# Memory.net
KiCad netlist of a schematic drawn in Altium Designer
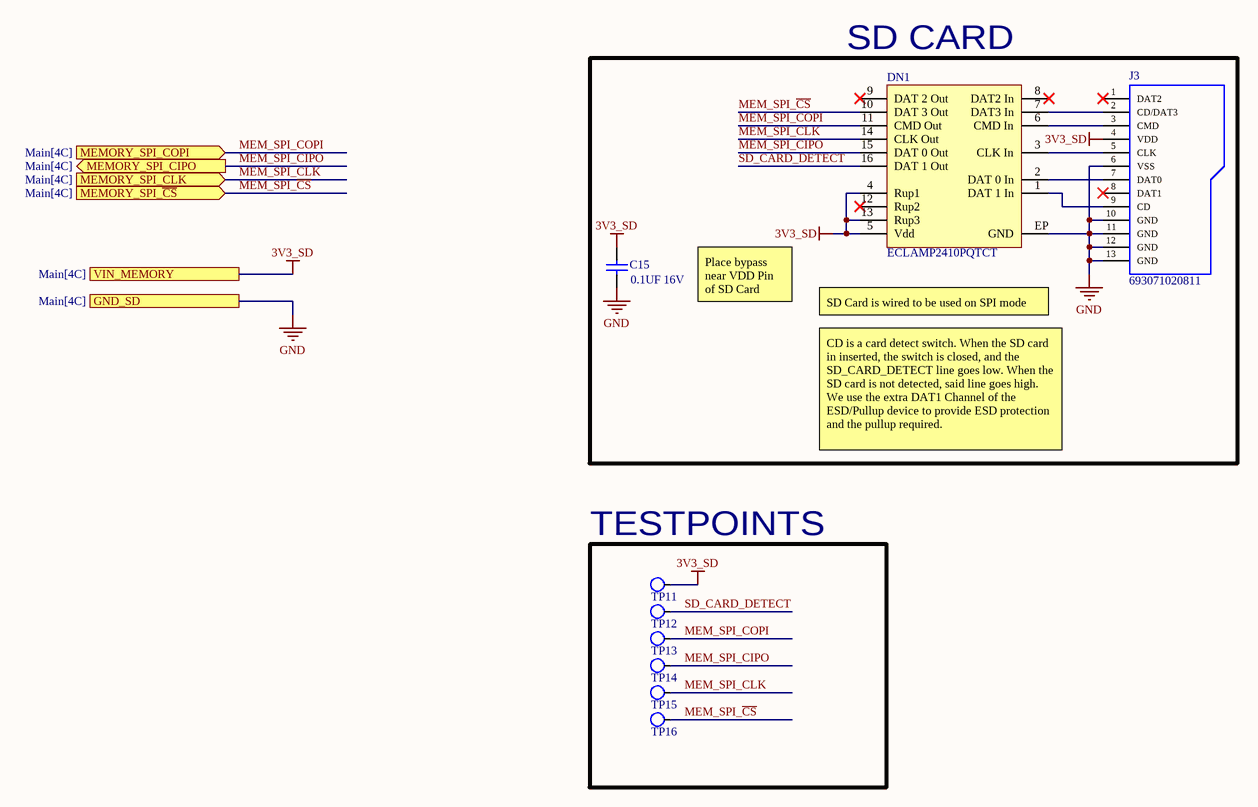
[diagram p0: Memory.SchDoc]

(export (version "E")
  (design (tool "Eeschema 10.0.6"))
  (components
    (comp (ref "C15")
      (value "0.1UF 16V")
      (footprint "0603_CAP")
      (description "Capacitor Surface Mount 0603 Footprint 0.1UF 16V 10% Tolerance Ceramic X7R")
      (fields (field (name "VOLTAGE") "16V") (field (name "MANUFACTURER") "Various"))
      (libsource (lib "University of Pennsylvania (ESE Labs)") (part "cap"))
    )
    (comp (ref "DN1")
      (value "ECLAMP2410PQTCT")
      (footprint "ECLAMP2410PQTCT-Footprint-1")
      (description "Trans Voltage Suppressor Diode, 5V V(RWM), Bidirectional, 7 Element, Silicon with EMI Filter")
      (libsource (lib "University of Pennsylvania (ESE)") (part "ECLAMP2410PQTCT-Symbol-1"))
    )
    (comp (ref "J3")
      (value "693071020811")
      (footprint "693071020811")
      (description "WR-CRD Micro SD Card Connector Push & Push")
      (fields (field (name "PUBLISHER") "Wurth Elektronik"))
      (libsource (lib "University of Pennsylvania (ESE)") (part "CMP-CON-00115-2"))
    )
    (comp (ref "TP11")
      (value "Testpad")
      (footprint "SMT Testpoint, 50mil")
      (description "Test Pad/Point (Testpoint, Testpad), for probing")
      (libsource (lib "University of Pennsylvania (ESE)") (part "30mm Test Pad"))
    )
    (comp (ref "TP12")
      (value "Testpad")
      (footprint "SMT Testpoint, 50mil")
      (description "Test Pad/Point (Testpoint, Testpad), for probing")
      (libsource (lib "University of Pennsylvania (ESE)") (part "30mm Test Pad"))
    )
    (comp (ref "TP13")
      (value "Testpad")
      (footprint "SMT Testpoint, 50mil")
      (description "Test Pad/Point (Testpoint, Testpad), for probing")
      (libsource (lib "University of Pennsylvania (ESE)") (part "30mm Test Pad"))
    )
    (comp (ref "TP14")
      (value "Testpad")
      (footprint "SMT Testpoint, 50mil")
      (description "Test Pad/Point (Testpoint, Testpad), for probing")
      (libsource (lib "University of Pennsylvania (ESE)") (part "30mm Test Pad"))
    )
    (comp (ref "TP15")
      (value "Testpad")
      (footprint "SMT Testpoint, 50mil")
      (description "Test Pad/Point (Testpoint, Testpad), for probing")
      (libsource (lib "University of Pennsylvania (ESE)") (part "30mm Test Pad"))
    )
    (comp (ref "TP16")
      (value "Testpad")
      (footprint "SMT Testpoint, 50mil")
      (description "Test Pad/Point (Testpoint, Testpad), for probing")
      (libsource (lib "University of Pennsylvania (ESE)") (part "30mm Test Pad"))
    )
  )
  (nets
    (net (code "1") (name "/MEM_SPI_CIPO") (class "Default")
      (node (ref "DN1") (pin "15") (pinfunction "DAT_0_Out_15") (pintype "passive"))
      (node (ref "TP14") (pin "1") (pinfunction "1_1") (pintype "passive"))
    )
    (net (code "2") (name "/MEM_SPI_CLK") (class "Default")
      (node (ref "DN1") (pin "14") (pinfunction "CLK_Out_14") (pintype "passive"))
      (node (ref "TP15") (pin "1") (pinfunction "1_1") (pintype "passive"))
    )
    (net (code "3") (name "/MEM_SPI_COPI") (class "Default")
      (node (ref "DN1") (pin "11") (pinfunction "CMD_Out_11") (pintype "passive"))
      (node (ref "TP13") (pin "1") (pinfunction "1_1") (pintype "passive"))
    )
    (net (code "4") (name "/MEM_SPI_~{CS}") (class "Default")
      (node (ref "DN1") (pin "10") (pinfunction "DAT_3_Out_10") (pintype "passive"))
      (node (ref "TP16") (pin "1") (pinfunction "1_1") (pintype "passive"))
    )
    (net (code "5") (name "/SD_CARD_DETECT") (class "Default")
      (node (ref "DN1") (pin "16") (pinfunction "DAT_1_Out_16") (pintype "passive"))
      (node (ref "TP12") (pin "1") (pinfunction "1_1") (pintype "passive"))
    )
    (net (code "6") (name "3V3_SD") (class "Default")
      (node (ref "C15") (pin "2") (pinfunction "2_2") (pintype "passive"))
      (node (ref "DN1") (pin "13") (pinfunction "Rup3_13") (pintype "power_in"))
      (node (ref "DN1") (pin "4") (pinfunction "Rup1_4") (pintype "power_in"))
      (node (ref "DN1") (pin "5") (pinfunction "Vdd_5") (pintype "power_in"))
      (node (ref "J3") (pin "4") (pinfunction "VDD_4") (pintype "passive"))
      (node (ref "TP11") (pin "1") (pinfunction "1_1") (pintype "passive"))
    )
    (net (code "7") (name "GND") (class "Default")
      (node (ref "C15") (pin "1") (pinfunction "1_1") (pintype "passive"))
      (node (ref "DN1") (pin "EP") (pinfunction "GND_EP") (pintype "power_in"))
      (node (ref "J3") (pin "10") (pinfunction "GND_10") (pintype "passive"))
      (node (ref "J3") (pin "11") (pinfunction "GND_11") (pintype "passive"))
      (node (ref "J3") (pin "12") (pinfunction "GND_12") (pintype "passive"))
      (node (ref "J3") (pin "13") (pinfunction "GND_13") (pintype "passive"))
      (node (ref "J3") (pin "6") (pinfunction "VSS_6") (pintype "passive"))
    )
    (net (code "8") (name "Net-(DN1-CLK_In)") (class "Default")
      (node (ref "DN1") (pin "3") (pinfunction "CLK_In_3") (pintype "passive"))
      (node (ref "J3") (pin "5") (pinfunction "CLK_5") (pintype "passive"))
    )
    (net (code "9") (name "Net-(DN1-CMD_In)") (class "Default")
      (node (ref "DN1") (pin "6") (pinfunction "CMD_In_6") (pintype "passive"))
      (node (ref "J3") (pin "3") (pinfunction "CMD_3") (pintype "passive"))
    )
    (net (code "10") (name "Net-(DN1-DAT3_In)") (class "Default")
      (node (ref "DN1") (pin "7") (pinfunction "DAT3_In_7") (pintype "passive"))
      (node (ref "J3") (pin "2") (pinfunction "CD/DAT3_2") (pintype "passive"))
    )
    (net (code "11") (name "Net-(DN1-DAT_0_In)") (class "Default")
      (node (ref "DN1") (pin "2") (pinfunction "DAT_0_In_2") (pintype "passive"))
      (node (ref "J3") (pin "7") (pinfunction "DAT0_7") (pintype "passive"))
    )
    (net (code "12") (name "Net-(DN1-DAT_1_In)") (class "Default")
      (node (ref "DN1") (pin "1") (pinfunction "DAT_1_In_1") (pintype "passive"))
      (node (ref "J3") (pin "9") (pinfunction "CD_9") (pintype "passive"))
    )
    (net (code "13") (name "unconnected-(DN1-DAT2_In-Pad8)") (class "Default")
      (node (ref "DN1") (pin "8") (pinfunction "DAT2_In_8") (pintype "passive+no_connect"))
    )
    (net (code "14") (name "unconnected-(DN1-DAT_2_Out-Pad9)") (class "Default")
      (node (ref "DN1") (pin "9") (pinfunction "DAT_2_Out_9") (pintype "passive+no_connect"))
    )
    (net (code "15") (name "unconnected-(DN1-Rup2-Pad12)") (class "Default")
      (node (ref "DN1") (pin "12") (pinfunction "Rup2_12") (pintype "power_in+no_connect"))
    )
    (net (code "16") (name "unconnected-(J3-DAT1-Pad8)") (class "Default")
      (node (ref "J3") (pin "8") (pinfunction "DAT1_8") (pintype "passive+no_connect"))
    )
    (net (code "17") (name "unconnected-(J3-DAT2-Pad1)") (class "Default")
      (node (ref "J3") (pin "1") (pinfunction "DAT2_1") (pintype "passive+no_connect"))
    )
  )
)
